# CH32V007K8U6-R0.net
KiCad netlist of a schematic drawn in Altium Designer
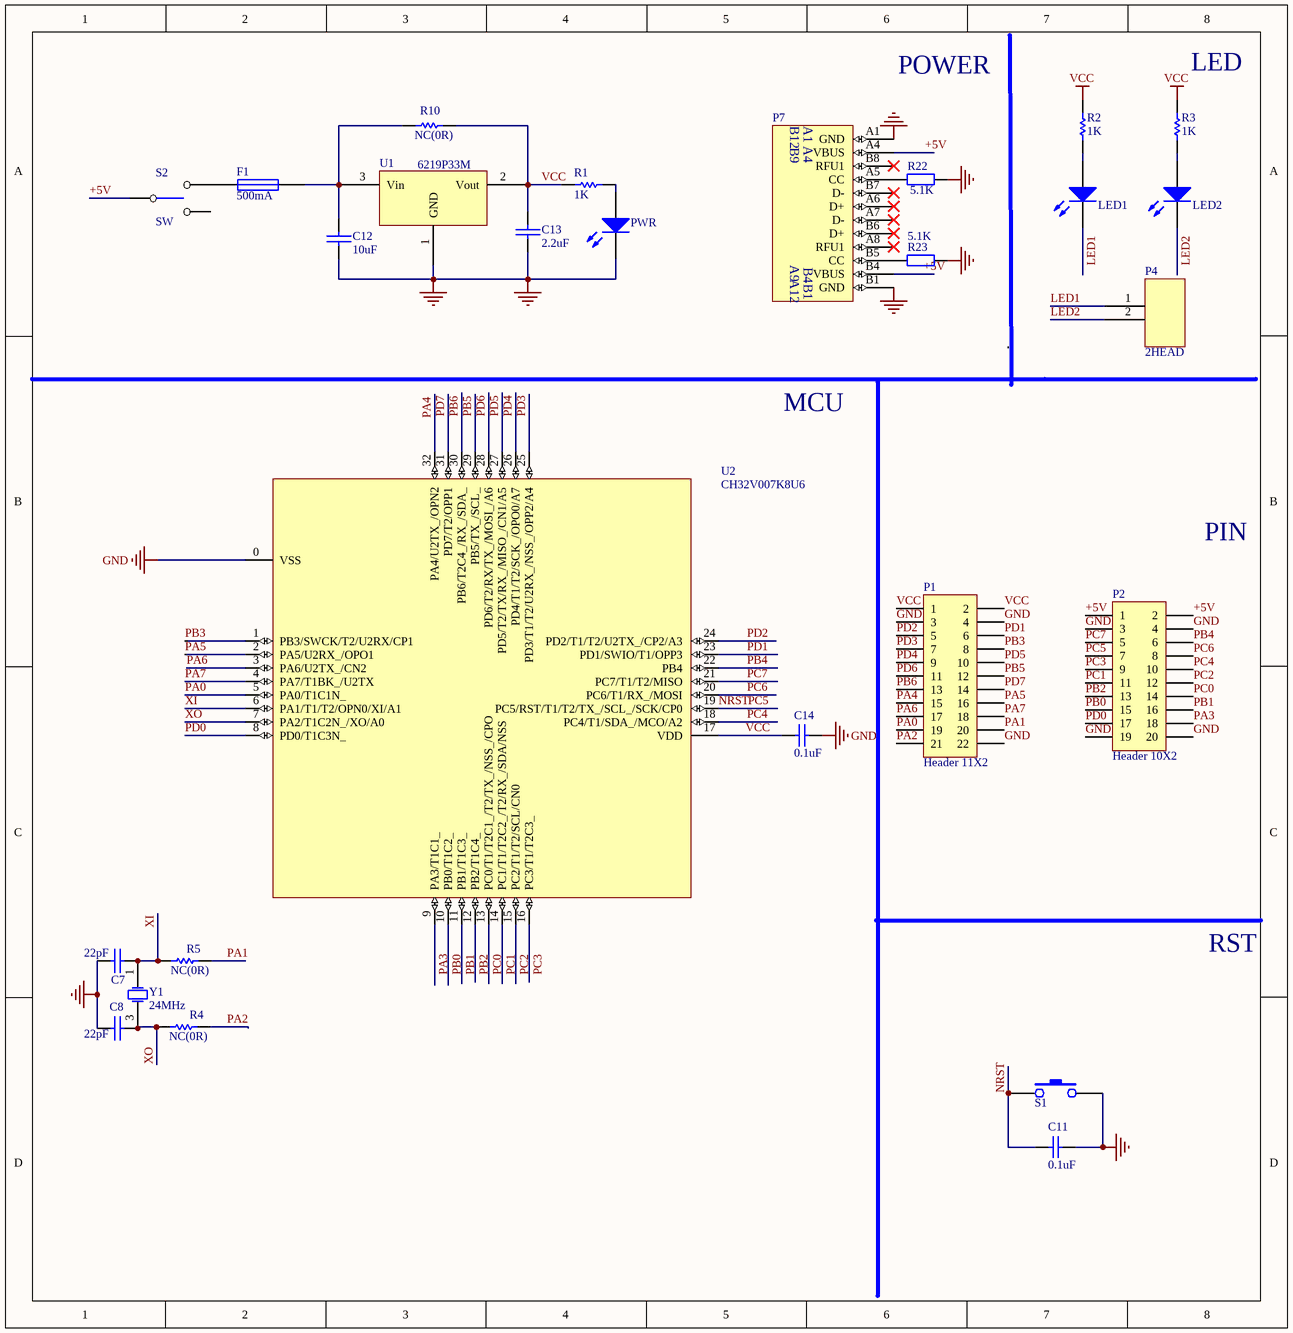
[diagram p0: CH32V007K8U6-R0.SchDoc]

(export (version "E")
  (design (tool "Eeschema 10.0.6"))
  (components
    (comp (ref "C7")
      (value "22pF")
      (footprint "0402_C")
      (description "Capacitor")
      (libsource (lib "*") (part "CAP"))
    )
    (comp (ref "C8")
      (value "22pF")
      (footprint "0402_C")
      (description "Capacitor")
      (libsource (lib "*") (part "CAP"))
    )
    (comp (ref "C11")
      (value "0.1uF")
      (footprint "0402_C")
      (description "Capacitor")
      (fields (field (name "PUBLISHER") "Altium Limited"))
      (libsource (lib "*") (part "Cap"))
    )
    (comp (ref "C12")
      (value "10uF")
      (footprint "0603_C")
      (description "Capacitor")
      (libsource (lib "wch_sch_others") (part "CAP"))
    )
    (comp (ref "C13")
      (value "2.2uF")
      (footprint "0402_C")
      (description "Capacitor")
      (libsource (lib "wch_sch_others") (part "CAP"))
    )
    (comp (ref "C14")
      (value "0.1uF")
      (footprint "0402_C")
      (description "Capacitor")
      (fields (field (name "PUBLISHER") "Altium Limited"))
      (libsource (lib "*") (part "Cap"))
    )
    (comp (ref "F1")
      (value "500mA")
      (footprint "0603")
      (description "Fuse")
      (libsource (lib "*") (part "FUSE1"))
    )
    (comp (ref "LED1")
      (value "LED1   blue")
      (footprint "0603+")
      (description "Typical INFRARED GaAs LED")
      (fields (field (name "PUBLISHER") "Altium Limited"))
      (libsource (lib "*") (part "LED0"))
    )
    (comp (ref "LED2")
      (value "LED2  blue")
      (footprint "0603+")
      (description "Typical INFRARED GaAs LED")
      (fields (field (name "PUBLISHER") "Altium Limited"))
      (libsource (lib "*") (part "LED0"))
    )
    (comp (ref "P1")
      (value "Header 11X2")
      (footprint "IDC22-2.54mm")
      (description "Header, 11-Pin, Dual row")
      (fields (field (name "PUBLISHER") "Altium Limited"))
      (libsource (lib "Miscellaneous Connectors") (part "Header 11X2"))
    )
    (comp (ref "P2")
      (value "Header 10X2")
      (footprint "IDC20-2.54mm")
      (description "Header, 10-Pin, Dual row")
      (fields (field (name "PUBLISHER") "Altium Limited"))
      (libsource (lib "Miscellaneous Connectors") (part "Header 10X2"))
    )
    (comp (ref "P4") (value "2HEAD") (footprint "SIP2-2.54mm") (libsource (lib "*") (part "2HEAD")))
    (comp (ref "P7")
      (value "TYPE-C")
      (footprint "TYPE-C-Receptacle-2.0")
      (libsource (lib "*") (part "TYPE-C1"))
    )
    (comp (ref "PWR")
      (value "POWER  red")
      (footprint "0603+")
      (description "Typical INFRARED GaAs LED")
      (fields (field (name "PUBLISHER") "Altium Limited"))
      (libsource (lib "") (part "LED0_1"))
    )
    (comp (ref "R1")
      (value "1K")
      (footprint "0402")
      (description "Semiconductor Resistor")
      (fields (field (name "PUBLISHER") "Altium Limited"))
      (libsource (lib "*") (part "Res Semi"))
    )
    (comp (ref "R2")
      (value "1K")
      (footprint "0402")
      (description "Semiconductor Resistor")
      (fields (field (name "PUBLISHER") "Altium Limited"))
      (libsource (lib "*") (part "Res Semi"))
    )
    (comp (ref "R3")
      (value "1K")
      (footprint "0402")
      (description "Semiconductor Resistor")
      (fields (field (name "PUBLISHER") "Altium Limited"))
      (libsource (lib "*") (part "Res Semi"))
    )
    (comp (ref "R4")
      (value "NC(0R)")
      (footprint "0402")
      (description "Semiconductor Resistor")
      (fields (field (name "Comment") "0R") (field (name "PUBLISHER") "Altium Limited"))
      (libsource (lib "*") (part "Res Semi"))
    )
    (comp (ref "R5")
      (value "NC(0R)")
      (footprint "0402")
      (description "Semiconductor Resistor")
      (fields (field (name "Comment") "0R") (field (name "PUBLISHER") "Altium Limited"))
      (libsource (lib "*") (part "Res Semi"))
    )
    (comp (ref "R10")
      (value "NC(0R)")
      (footprint "0402")
      (description "Semiconductor Resistor")
      (fields (field (name "Comment") "0R") (field (name "PUBLISHER") "Altium Limited"))
      (libsource (lib "*") (part "Res Semi"))
    )
    (comp (ref "R22")
      (value "5.1K")
      (footprint "0402")
      (description "Resistor")
      (libsource (lib "Miscellaneous Devices") (part "Res2"))
    )
    (comp (ref "R23")
      (value "5.1K")
      (footprint "0402")
      (description "Resistor")
      (libsource (lib "Miscellaneous Devices") (part "Res2"))
    )
    (comp (ref "S1") (value "NRST") (footprint "SMD_6.1x3.65x2.5mm-KEY") (libsource (lib "*") (part "KEY")))
    (comp (ref "S2") (value "SW") (footprint "SW1") (libsource (lib "*") (part "SW")))
    (comp (ref "U1")
      (value "6219P33M")
      (footprint "SOT-23")
      (libsource (lib "wch_sch_others") (part "6219P33M"))
    )
    (comp (ref "U2")
      (value "CH32V007K8U6")
      (footprint "QFN32_4X4")
      (description "RISC-V MCU, ADC/OPA/CMP/2*UART/I2C/SPI")
      (libsource (lib "CHXXX(2)") (part "CH32V007K8U6"))
    )
    (comp (ref "Y1")
      (value "24MHz")
      (footprint "XT3225")
      (description "Crystal Oscillator")
      (fields (field (name "PUBLISHER") "Altium Limited"))
      (libsource (lib "*") (part "XTAL"))
    )
  )
  (nets
    (net (code "1") (name "/+5V") (class "Default")
      (node (ref "P2") (pin "1") (pinfunction "1_1") (pintype "passive"))
      (node (ref "P2") (pin "2") (pinfunction "2_2") (pintype "passive"))
      (node (ref "P7") (pin "A4") (pinfunction "VBUS_A4") (pintype "bidirectional"))
      (node (ref "P7") (pin "B4") (pinfunction "VBUS_B4") (pintype "bidirectional"))
      (node (ref "S2") (pin "1") (pinfunction "1_1") (pintype "passive"))
    )
    (net (code "2") (name "/LED1") (class "Default")
      (node (ref "LED1") (pin "2") (pinfunction "K_2") (pintype "passive"))
      (node (ref "P4") (pin "1") (pintype "passive"))
    )
    (net (code "3") (name "/LED2") (class "Default")
      (node (ref "LED2") (pin "2") (pinfunction "K_2") (pintype "passive"))
      (node (ref "P4") (pin "2") (pintype "passive"))
    )
    (net (code "4") (name "/NRST") (class "Default")
      (node (ref "C11") (pin "2") (pinfunction "2_2") (pintype "passive"))
      (node (ref "P2") (pin "7") (pinfunction "7_7") (pintype "passive"))
      (node (ref "S1") (pin "1") (pinfunction "1_1") (pintype "passive"))
      (node (ref "U2") (pin "19") (pinfunction "PC5/RST/T1/T2/TX_/SCL_/SCK/CP0_19") (pintype "bidirectional"))
    )
    (net (code "5") (name "/PA0") (class "Default")
      (node (ref "P1") (pin "19") (pinfunction "19_19") (pintype "passive"))
      (node (ref "U2") (pin "5") (pinfunction "PA0/T1C1N__5") (pintype "bidirectional"))
    )
    (net (code "6") (name "/PA1") (class "Default")
      (node (ref "P1") (pin "20") (pinfunction "20_20") (pintype "passive"))
      (node (ref "R5") (pin "2") (pinfunction "2_2") (pintype "passive"))
    )
    (net (code "7") (name "/PA2") (class "Default")
      (node (ref "P1") (pin "21") (pinfunction "21_21") (pintype "passive"))
      (node (ref "R4") (pin "2") (pinfunction "2_2") (pintype "passive"))
    )
    (net (code "8") (name "/PA3") (class "Default")
      (node (ref "P2") (pin "18") (pinfunction "18_18") (pintype "passive"))
      (node (ref "U2") (pin "9") (pinfunction "PA3/T1C1__9") (pintype "bidirectional"))
    )
    (net (code "9") (name "/PA4") (class "Default")
      (node (ref "P1") (pin "15") (pinfunction "15_15") (pintype "passive"))
      (node (ref "U2") (pin "32") (pinfunction "PA4/U2TX_/OPN2_32") (pintype "bidirectional"))
    )
    (net (code "10") (name "/PA5") (class "Default")
      (node (ref "P1") (pin "16") (pinfunction "16_16") (pintype "passive"))
      (node (ref "U2") (pin "2") (pinfunction "PA5/U2RX_/OPO1_2") (pintype "bidirectional"))
    )
    (net (code "11") (name "/PA6") (class "Default")
      (node (ref "P1") (pin "17") (pinfunction "17_17") (pintype "passive"))
      (node (ref "U2") (pin "3") (pinfunction "PA6/U2TX_/CN2_3") (pintype "bidirectional"))
    )
    (net (code "12") (name "/PA7") (class "Default")
      (node (ref "P1") (pin "18") (pinfunction "18_18") (pintype "passive"))
      (node (ref "U2") (pin "4") (pinfunction "PA7/T1BK_/U2TX_4") (pintype "bidirectional"))
    )
    (net (code "13") (name "/PB0") (class "Default")
      (node (ref "P2") (pin "15") (pinfunction "15_15") (pintype "passive"))
      (node (ref "U2") (pin "10") (pinfunction "PB0/T1C2__10") (pintype "bidirectional"))
    )
    (net (code "14") (name "/PB1") (class "Default")
      (node (ref "P2") (pin "16") (pinfunction "16_16") (pintype "passive"))
      (node (ref "U2") (pin "11") (pinfunction "PB1/T1C3__11") (pintype "bidirectional"))
    )
    (net (code "15") (name "/PB2") (class "Default")
      (node (ref "P2") (pin "13") (pinfunction "13_13") (pintype "passive"))
      (node (ref "U2") (pin "12") (pinfunction "PB2/T1C4__12") (pintype "bidirectional"))
    )
    (net (code "16") (name "/PB3") (class "Default")
      (node (ref "P1") (pin "8") (pinfunction "8_8") (pintype "passive"))
      (node (ref "U2") (pin "1") (pinfunction "PB3/SWCK/T2/U2RX/CP1_1") (pintype "bidirectional"))
    )
    (net (code "17") (name "/PB4") (class "Default")
      (node (ref "P2") (pin "6") (pinfunction "6_6") (pintype "passive"))
      (node (ref "U2") (pin "22") (pinfunction "PB4_22") (pintype "bidirectional"))
    )
    (net (code "18") (name "/PB5") (class "Default")
      (node (ref "P1") (pin "12") (pinfunction "12_12") (pintype "passive"))
      (node (ref "U2") (pin "29") (pinfunction "PB5/TX_/SCL__29") (pintype "bidirectional"))
    )
    (net (code "19") (name "/PB6") (class "Default")
      (node (ref "P1") (pin "13") (pinfunction "13_13") (pintype "passive"))
      (node (ref "U2") (pin "30") (pinfunction "PB6/T2C4_/RX_/SDA__30") (pintype "bidirectional"))
    )
    (net (code "20") (name "/PC0") (class "Default")
      (node (ref "P2") (pin "14") (pinfunction "14_14") (pintype "passive"))
      (node (ref "U2") (pin "13") (pinfunction "PC0/T1/T2C1_/T2/TX_/NSS_/CPO_13") (pintype "bidirectional"))
    )
    (net (code "21") (name "/PC1") (class "Default")
      (node (ref "P2") (pin "11") (pinfunction "11_11") (pintype "passive"))
      (node (ref "U2") (pin "14") (pinfunction "PC1/T1/T2C2_/T2/RX_/SDA/NSS_14") (pintype "bidirectional"))
    )
    (net (code "22") (name "/PC2") (class "Default")
      (node (ref "P2") (pin "12") (pinfunction "12_12") (pintype "passive"))
      (node (ref "U2") (pin "15") (pinfunction "PC2/T1/T2/SCL/CN0_15") (pintype "bidirectional"))
    )
    (net (code "23") (name "/PC3") (class "Default")
      (node (ref "P2") (pin "9") (pinfunction "9_9") (pintype "passive"))
      (node (ref "U2") (pin "16") (pinfunction "PC3/T1/T2C3__16") (pintype "bidirectional"))
    )
    (net (code "24") (name "/PC4") (class "Default")
      (node (ref "P2") (pin "10") (pinfunction "10_10") (pintype "passive"))
      (node (ref "U2") (pin "18") (pinfunction "PC4/T1/SDA_/MCO/A2_18") (pintype "bidirectional"))
    )
    (net (code "25") (name "/PC6") (class "Default")
      (node (ref "P2") (pin "8") (pinfunction "8_8") (pintype "passive"))
      (node (ref "U2") (pin "20") (pinfunction "PC6/T1/RX_/MOSI_20") (pintype "bidirectional"))
    )
    (net (code "26") (name "/PC7") (class "Default")
      (node (ref "P2") (pin "5") (pinfunction "5_5") (pintype "passive"))
      (node (ref "U2") (pin "21") (pinfunction "PC7/T1/T2/MISO_21") (pintype "bidirectional"))
    )
    (net (code "27") (name "/PD0") (class "Default")
      (node (ref "P2") (pin "17") (pinfunction "17_17") (pintype "passive"))
      (node (ref "U2") (pin "8") (pinfunction "PD0/T1C3N__8") (pintype "bidirectional"))
    )
    (net (code "28") (name "/PD1") (class "Default")
      (node (ref "P1") (pin "6") (pinfunction "6_6") (pintype "passive"))
      (node (ref "U2") (pin "23") (pinfunction "PD1/SWIO/T1/OPP3_23") (pintype "bidirectional"))
    )
    (net (code "29") (name "/PD2") (class "Default")
      (node (ref "P1") (pin "5") (pinfunction "5_5") (pintype "passive"))
      (node (ref "U2") (pin "24") (pinfunction "PD2/T1/T2/U2TX_/CP2/A3_24") (pintype "bidirectional"))
    )
    (net (code "30") (name "/PD3") (class "Default")
      (node (ref "P1") (pin "7") (pinfunction "7_7") (pintype "passive"))
      (node (ref "U2") (pin "25") (pinfunction "PD3/T1/T2/U2RX_/NSS_/OPP2/A4_25") (pintype "bidirectional"))
    )
    (net (code "31") (name "/PD4") (class "Default")
      (node (ref "P1") (pin "9") (pinfunction "9_9") (pintype "passive"))
      (node (ref "U2") (pin "26") (pinfunction "PD4/T1/T2/SCK_/OPO0/A7_26") (pintype "bidirectional"))
    )
    (net (code "32") (name "/PD5") (class "Default")
      (node (ref "P1") (pin "10") (pinfunction "10_10") (pintype "passive"))
      (node (ref "U2") (pin "27") (pinfunction "PD5/T2/TX/RX_/MISO_/CN1/A5_27") (pintype "bidirectional"))
    )
    (net (code "33") (name "/PD6") (class "Default")
      (node (ref "P1") (pin "11") (pinfunction "11_11") (pintype "passive"))
      (node (ref "U2") (pin "28") (pinfunction "PD6/T2/RX/TX_/MOSI_/A6_28") (pintype "bidirectional"))
    )
    (net (code "34") (name "/PD7") (class "Default")
      (node (ref "P1") (pin "14") (pinfunction "14_14") (pintype "passive"))
      (node (ref "U2") (pin "31") (pinfunction "PD7/T2/OPP1_31") (pintype "bidirectional"))
    )
    (net (code "35") (name "/XI") (class "Default")
      (node (ref "C7") (pin "2") (pinfunction "2_2") (pintype "passive"))
      (node (ref "R5") (pin "1") (pinfunction "1_1") (pintype "passive"))
      (node (ref "U2") (pin "6") (pinfunction "PA1/T1/T2/OPN0/XI/A1_6") (pintype "bidirectional"))
      (node (ref "Y1") (pin "1") (pinfunction "OSC1_1") (pintype "passive"))
    )
    (net (code "36") (name "/XO") (class "Default")
      (node (ref "C8") (pin "2") (pinfunction "2_2") (pintype "passive"))
      (node (ref "R4") (pin "1") (pinfunction "1_1") (pintype "passive"))
      (node (ref "U2") (pin "7") (pinfunction "PA2/T1C2N_/XO/A0_7") (pintype "bidirectional"))
      (node (ref "Y1") (pin "3") (pinfunction "OSC2_3") (pintype "passive"))
    )
    (net (code "37") (name "GND") (class "Default")
      (node (ref "C11") (pin "1") (pinfunction "1_1") (pintype "passive"))
      (node (ref "C12") (pin "2") (pinfunction "2_2") (pintype "passive"))
      (node (ref "C13") (pin "1") (pinfunction "1_1") (pintype "passive"))
      (node (ref "C14") (pin "2") (pinfunction "2_2") (pintype "passive"))
      (node (ref "C7") (pin "1") (pinfunction "1_1") (pintype "passive"))
      (node (ref "C8") (pin "1") (pinfunction "1_1") (pintype "passive"))
      (node (ref "P1") (pin "22") (pinfunction "22_22") (pintype "passive"))
      (node (ref "P1") (pin "3") (pinfunction "3_3") (pintype "passive"))
      (node (ref "P1") (pin "4") (pinfunction "4_4") (pintype "passive"))
      (node (ref "P2") (pin "19") (pinfunction "19_19") (pintype "passive"))
      (node (ref "P2") (pin "20") (pinfunction "20_20") (pintype "passive"))
      (node (ref "P2") (pin "3") (pinfunction "3_3") (pintype "passive"))
      (node (ref "P2") (pin "4") (pinfunction "4_4") (pintype "passive"))
      (node (ref "P7") (pin "A1") (pinfunction "GND_A1") (pintype "bidirectional"))
      (node (ref "P7") (pin "B1") (pinfunction "GND_B1") (pintype "bidirectional"))
      (node (ref "PWR") (pin "2") (pinfunction "K_2") (pintype "passive"))
      (node (ref "R22") (pin "2") (pinfunction "2_2") (pintype "passive"))
      (node (ref "R23") (pin "2") (pinfunction "2_2") (pintype "passive"))
      (node (ref "S1") (pin "2") (pinfunction "2_2") (pintype "passive"))
      (node (ref "U1") (pin "1") (pinfunction "GND_1") (pintype "passive"))
      (node (ref "U2") (pin "0") (pinfunction "VSS_0") (pintype "power_in"))
    )
    (net (code "38") (name "Net-(F1-Pad1)") (class "Default")
      (node (ref "F1") (pin "1") (pinfunction "1_1") (pintype "passive"))
      (node (ref "S2") (pin "3") (pinfunction "3_3") (pintype "passive"))
    )
    (net (code "39") (name "Net-(LED1-A)") (class "Default")
      (node (ref "LED1") (pin "1") (pinfunction "A_1") (pintype "passive"))
      (node (ref "R2") (pin "2") (pinfunction "2_2") (pintype "passive"))
    )
    (net (code "40") (name "Net-(LED2-A)") (class "Default")
      (node (ref "LED2") (pin "1") (pinfunction "A_1") (pintype "passive"))
      (node (ref "R3") (pin "2") (pinfunction "2_2") (pintype "passive"))
    )
    (net (code "41") (name "Net-(P7-CC-PadA5)") (class "Default")
      (node (ref "P7") (pin "A5") (pinfunction "CC_A5") (pintype "bidirectional"))
      (node (ref "R22") (pin "1") (pinfunction "1_1") (pintype "passive"))
    )
    (net (code "42") (name "Net-(P7-CC-PadB5)") (class "Default")
      (node (ref "P7") (pin "B5") (pinfunction "CC_B5") (pintype "bidirectional"))
      (node (ref "R23") (pin "1") (pinfunction "1_1") (pintype "passive"))
    )
    (net (code "43") (name "Net-(PWR-A)") (class "Default")
      (node (ref "PWR") (pin "1") (pinfunction "A_1") (pintype "passive"))
      (node (ref "R1") (pin "1") (pinfunction "1_1") (pintype "passive"))
    )
    (net (code "44") (name "Net-(U1-Vin)") (class "Default")
      (node (ref "C12") (pin "1") (pinfunction "1_1") (pintype "passive"))
      (node (ref "F1") (pin "2") (pinfunction "2_2") (pintype "passive"))
      (node (ref "R10") (pin "1") (pinfunction "1_1") (pintype "passive"))
      (node (ref "U1") (pin "3") (pinfunction "Vin_3") (pintype "passive"))
    )
    (net (code "45") (name "VCC") (class "Default")
      (node (ref "C13") (pin "2") (pinfunction "2_2") (pintype "passive"))
      (node (ref "C14") (pin "1") (pinfunction "1_1") (pintype "passive"))
      (node (ref "P1") (pin "1") (pinfunction "1_1") (pintype "passive"))
      (node (ref "P1") (pin "2") (pinfunction "2_2") (pintype "passive"))
      (node (ref "R1") (pin "2") (pinfunction "2_2") (pintype "passive"))
      (node (ref "R10") (pin "2") (pinfunction "2_2") (pintype "passive"))
      (node (ref "R2") (pin "1") (pinfunction "1_1") (pintype "passive"))
      (node (ref "R3") (pin "1") (pinfunction "1_1") (pintype "passive"))
      (node (ref "U1") (pin "2") (pinfunction "Vout_2") (pintype "passive"))
      (node (ref "U2") (pin "17") (pinfunction "VDD_17") (pintype "power_in"))
    )
    (net (code "46") (name "unconnected-(P7-D+-PadA6)") (class "Default")
      (node (ref "P7") (pin "A6") (pinfunction "D+_A6") (pintype "bidirectional+no_connect"))
    )
    (net (code "47") (name "unconnected-(P7-D+-PadB6)") (class "Default")
      (node (ref "P7") (pin "B6") (pinfunction "D+_B6") (pintype "bidirectional+no_connect"))
    )
    (net (code "48") (name "unconnected-(P7-D--PadA7)") (class "Default")
      (node (ref "P7") (pin "A7") (pinfunction "D-_A7") (pintype "bidirectional+no_connect"))
    )
    (net (code "49") (name "unconnected-(P7-D--PadB7)") (class "Default")
      (node (ref "P7") (pin "B7") (pinfunction "D-_B7") (pintype "bidirectional+no_connect"))
    )
    (net (code "50") (name "unconnected-(P7-RFU1-PadA8)") (class "Default")
      (node (ref "P7") (pin "A8") (pinfunction "RFU1_A8") (pintype "bidirectional+no_connect"))
    )
    (net (code "51") (name "unconnected-(P7-RFU1-PadB8)") (class "Default")
      (node (ref "P7") (pin "B8") (pinfunction "RFU1_B8") (pintype "bidirectional+no_connect"))
    )
    (net (code "52") (name "unconnected-(S2-Pad2)") (class "Default")
      (node (ref "S2") (pin "2") (pinfunction "2_2") (pintype "passive"))
    )
  )
)
